# schemaElec_Protomesure.net
KiCad netlist of a schematic drawn in EAGLE
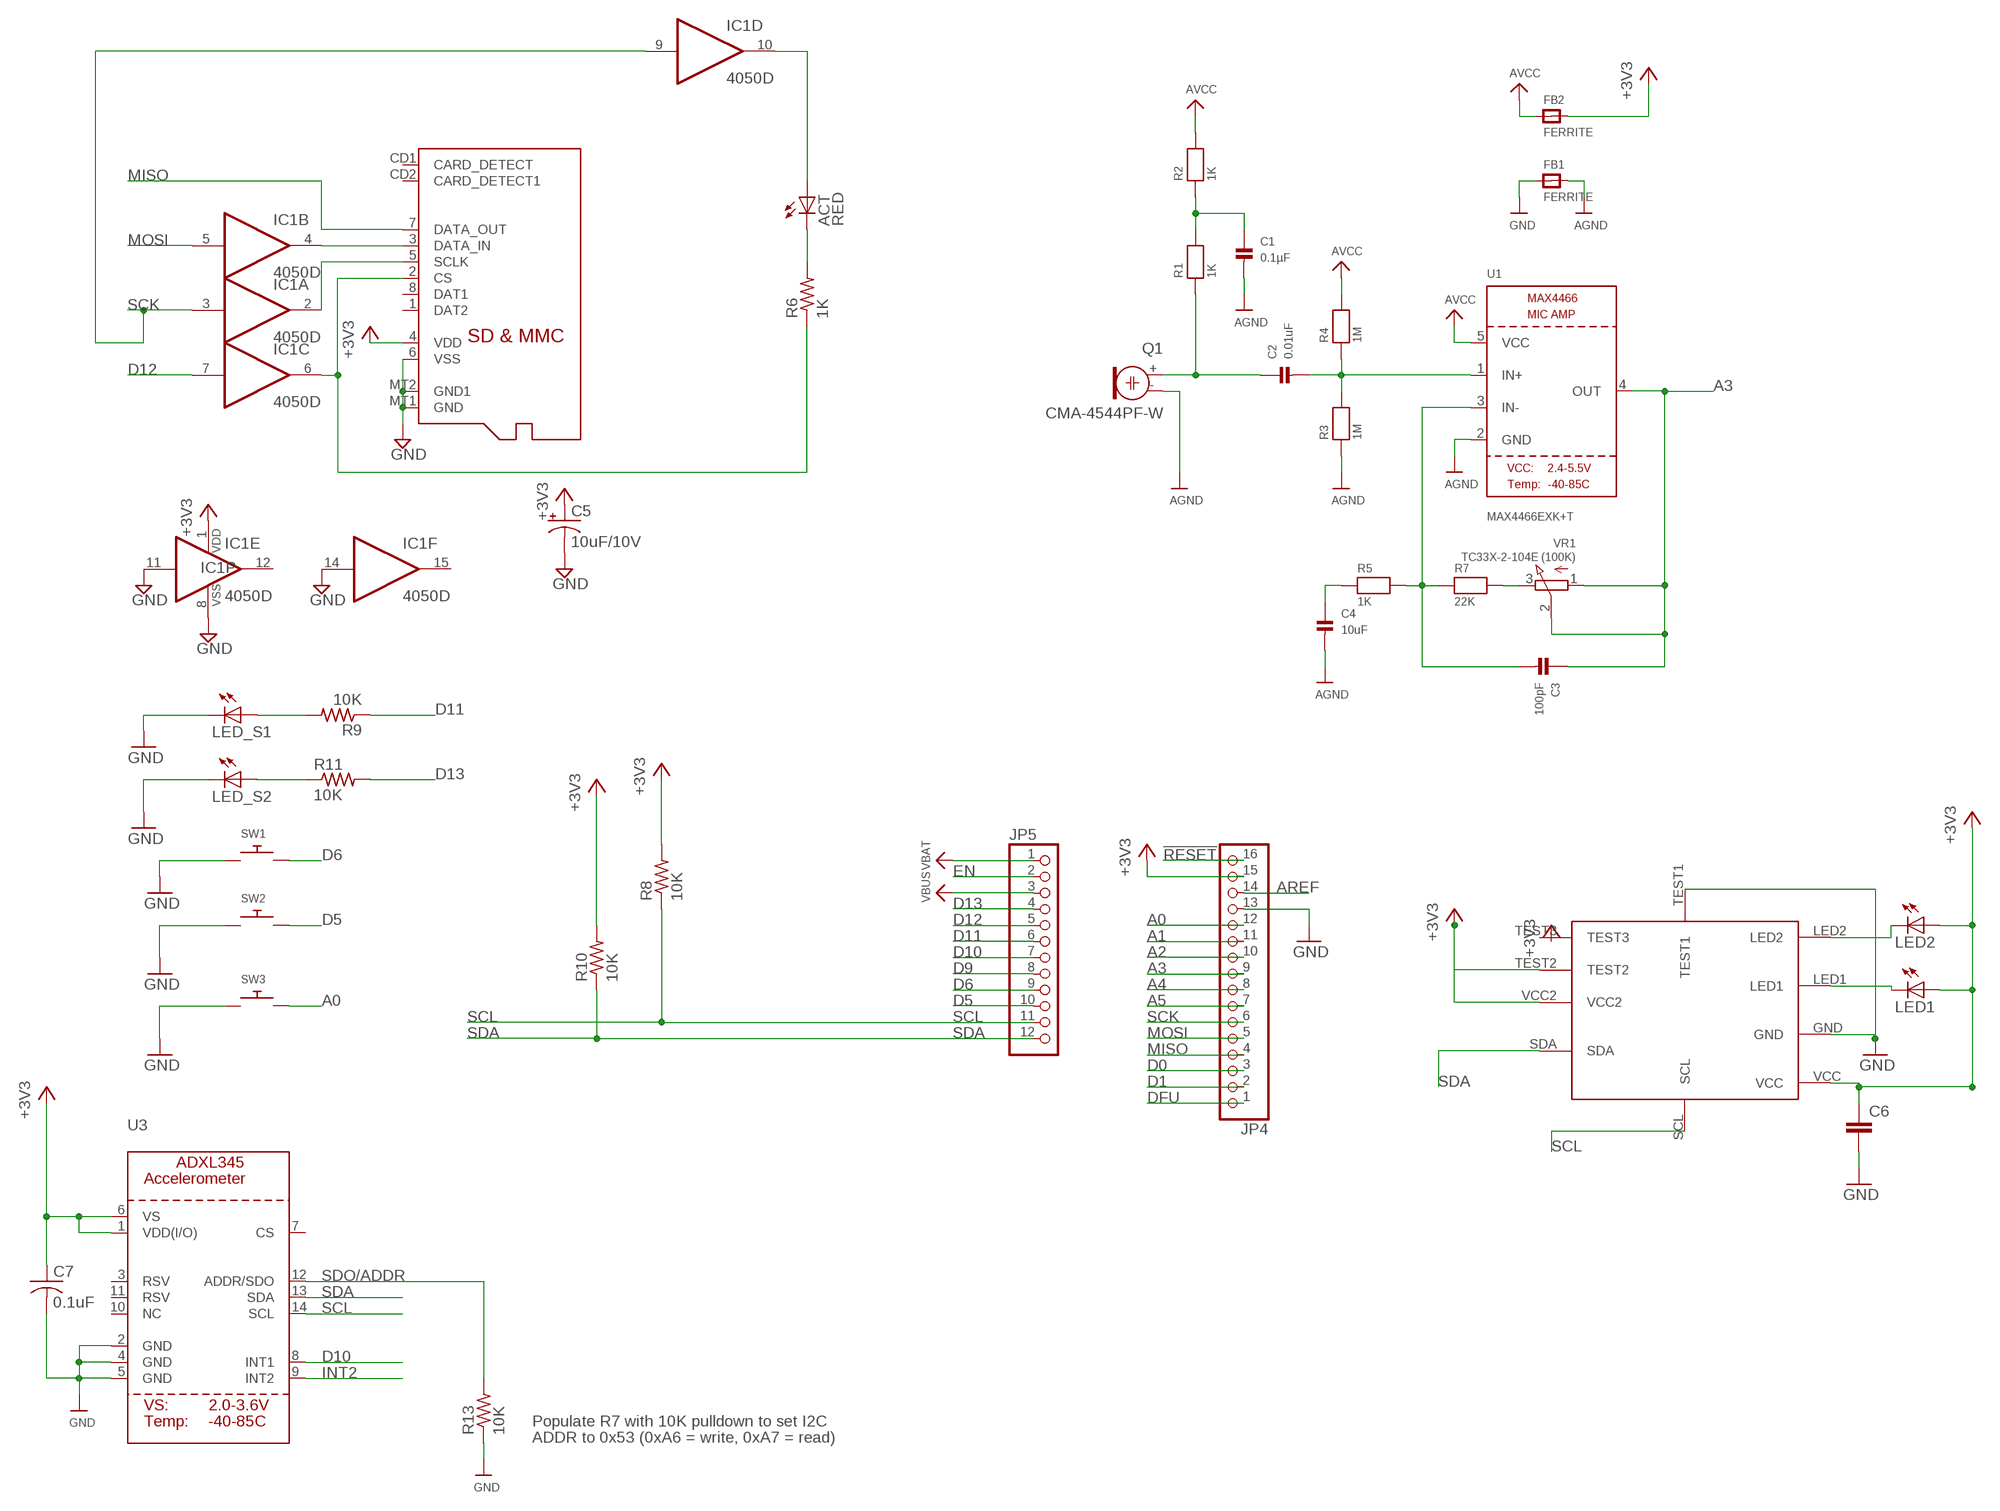
[diagram p0: schematic, sheet 1]

(export (version "E")
  (design (tool "Eeschema 10.0.6"))
  (components
    (comp (ref "ACT")
      (value "RED")
      (footprint "eagle-import:CHIP-LED0805")
      (libsource (lib "eagle-import") (part "LEDCHIP-LED0805"))
    )
    (comp (ref "C1")
      (value "0.1µF")
      (footprint "eagle-import:0805")
      (libsource (lib "eagle-import") (part "CAP_CERAMIC0805"))
    )
    (comp (ref "C2")
      (value "0.01uF")
      (footprint "eagle-import:0805")
      (libsource (lib "eagle-import") (part "CAP_CERAMIC0805"))
    )
    (comp (ref "C3")
      (value "100pF")
      (footprint "eagle-import:0805")
      (libsource (lib "eagle-import") (part "CAP_CERAMIC0805"))
    )
    (comp (ref "C4")
      (value "10uF")
      (footprint "eagle-import:0805")
      (libsource (lib "eagle-import") (part "CAP_CERAMIC0805"))
    )
    (comp (ref "C5")
      (value "10uF/10V")
      (footprint "eagle-import:A_3216-18R")
      (libsource (lib "eagle-import") (part "CPOL-USA/3216-18R"))
    )
    (comp (ref "C6")
      (value "C-EUC0805")
      (footprint "eagle-import:C0805")
      (libsource (lib "eagle-import") (part "C-EUC0805"))
    )
    (comp (ref "C7")
      (value "0.1uF")
      (footprint "eagle-import:C0805")
      (libsource (lib "eagle-import") (part "C-USC0805"))
    )
    (comp (ref "FB1")
      (value "FERRITE")
      (footprint "eagle-import:0805")
      (libsource (lib "eagle-import") (part "FERRITE0805"))
    )
    (comp (ref "FB2")
      (value "FERRITE")
      (footprint "eagle-import:0805")
      (libsource (lib "eagle-import") (part "FERRITE0805"))
    )
    (comp (ref "IC1")
      (value "4050D")
      (footprint "eagle-import:SO16")
      (libsource (lib "eagle-import") (part "4050D"))
    )
    (comp (ref "JP4")
      (value "HEADER-1X16ROUND")
      (footprint "eagle-import:1X16_ROUND")
      (libsource (lib "eagle-import") (part "HEADER-1X16ROUND"))
    )
    (comp (ref "JP5")
      (value "HEADER-1X12")
      (footprint "eagle-import:1X12_ROUND")
      (libsource (lib "eagle-import") (part "HEADER-1X12"))
    )
    (comp (ref "LED1")
      (value "LEDCHIPLED_0805")
      (footprint "eagle-import:CHIPLED_0805")
      (libsource (lib "eagle-import") (part "LEDCHIPLED_0805"))
    )
    (comp (ref "LED2")
      (value "LEDCHIPLED_0805")
      (footprint "eagle-import:CHIPLED_0805")
      (libsource (lib "eagle-import") (part "LEDCHIPLED_0805"))
    )
    (comp (ref "LED_S1")
      (value "LEDCHIPLED_0805")
      (footprint "eagle-import:CHIPLED_0805")
      (libsource (lib "eagle-import") (part "LEDCHIPLED_0805"))
    )
    (comp (ref "LED_S2")
      (value "LEDCHIPLED_0805")
      (footprint "eagle-import:CHIPLED_0805")
      (libsource (lib "eagle-import") (part "LEDCHIPLED_0805"))
    )
    (comp (ref "Q1")
      (value "CMA-4544PF-W")
      (footprint "eagle-import:ELECTRET_9.7")
      (libsource (lib "eagle-import") (part "ELECTRET"))
    )
    (comp (ref "R1")
      (value "1K")
      (footprint "eagle-import:0805")
      (libsource (lib "eagle-import") (part "RESISTOR0805"))
    )
    (comp (ref "R2")
      (value "1K")
      (footprint "eagle-import:0805")
      (libsource (lib "eagle-import") (part "RESISTOR0805"))
    )
    (comp (ref "R3")
      (value "1M")
      (footprint "eagle-import:0805")
      (libsource (lib "eagle-import") (part "RESISTOR0805"))
    )
    (comp (ref "R4")
      (value "1M")
      (footprint "eagle-import:0805")
      (libsource (lib "eagle-import") (part "RESISTOR0805"))
    )
    (comp (ref "R5")
      (value "1K")
      (footprint "eagle-import:0805")
      (libsource (lib "eagle-import") (part "RESISTOR0805"))
    )
    (comp (ref "R6")
      (value "1K")
      (footprint "eagle-import:R0805")
      (libsource (lib "eagle-import") (part "R-US_R0805"))
    )
    (comp (ref "R7")
      (value "22K")
      (footprint "eagle-import:0805")
      (libsource (lib "eagle-import") (part "RESISTOR0805"))
    )
    (comp (ref "R8")
      (value "10K")
      (footprint "eagle-import:R0805")
      (libsource (lib "eagle-import") (part "R-US_R0805"))
    )
    (comp (ref "R9")
      (value "10K")
      (footprint "eagle-import:R0805")
      (libsource (lib "eagle-import") (part "R-US_R0805"))
    )
    (comp (ref "R10")
      (value "10K")
      (footprint "eagle-import:R0805")
      (libsource (lib "eagle-import") (part "R-US_R0805"))
    )
    (comp (ref "R11")
      (value "10K")
      (footprint "eagle-import:R0805")
      (libsource (lib "eagle-import") (part "R-US_R0805"))
    )
    (comp (ref "R13")
      (value "10K")
      (footprint "eagle-import:R0805")
      (libsource (lib "eagle-import") (part "R-US_R0805"))
    )
    (comp (ref "SW1")
      (value "SWITCH_PUSHBUTTONEVQ-PE")
      (footprint "eagle-import:TACT_PANA-EVQ")
      (libsource (lib "eagle-import") (part "SWITCH_PUSHBUTTONEVQ-PE"))
    )
    (comp (ref "SW2")
      (value "SWITCH_PUSHBUTTONEVQ-PE")
      (footprint "eagle-import:TACT_PANA-EVQ")
      (libsource (lib "eagle-import") (part "SWITCH_PUSHBUTTONEVQ-PE"))
    )
    (comp (ref "SW3")
      (value "SWITCH_PUSHBUTTONEVQ-PE")
      (footprint "eagle-import:TACT_PANA-EVQ")
      (libsource (lib "eagle-import") (part "SWITCH_PUSHBUTTONEVQ-PE"))
    )
    (comp (ref "U$31")
      (value "BH1790")
      (footprint "eagle-import:BH1790")
      (libsource (lib "eagle-import") (part "BH1790"))
    )
    (comp (ref "U1")
      (value "MAX4466EXK+T")
      (footprint "eagle-import:SC70-5")
      (libsource (lib "eagle-import") (part "MAX4466{dblquote}{dblquote}"))
    )
    (comp (ref "U3")
      (value "ACCEL_ADXL345")
      (footprint "eagle-import:LGA14")
      (libsource (lib "eagle-import") (part "ACCEL_ADXL345"))
    )
    (comp (ref "VR1")
      (value "TC33X-2-104E (100K)")
      (footprint "eagle-import:TRIMPOT_BOURNS_TC33X-2")
      (libsource (lib "eagle-import") (part "TRIMPOTTC33X-2"))
    )
    (comp (ref "X1")
      (value "MICROSD")
      (footprint "eagle-import:MICROSD")
      (libsource (lib "eagle-import") (part "MICROSD"))
    )
  )
  (nets
    (net (code "1") (name "+3V3") (class "Default")
      (node (ref "C5") (pin "+") (pinfunction "+_+") (pintype "passive"))
      (node (ref "C6") (pin "1") (pinfunction "1_1") (pintype "passive"))
      (node (ref "C7") (pin "1") (pinfunction "1_1") (pintype "passive"))
      (node (ref "FB2") (pin "2") (pinfunction "P$2_2") (pintype "passive"))
      (node (ref "IC1") (pin "1") (pinfunction "VDD_1") (pintype "power_in"))
      (node (ref "JP4") (pin "15") (pinfunction "15_15") (pintype "passive"))
      (node (ref "LED1") (pin "A") (pinfunction "A_A") (pintype "passive"))
      (node (ref "LED2") (pin "A") (pinfunction "A_A") (pintype "passive"))
      (node (ref "R10") (pin "2") (pinfunction "2_2") (pintype "passive"))
      (node (ref "R8") (pin "2") (pinfunction "2_2") (pintype "passive"))
      (node (ref "U$31") (pin "TEST2") (pinfunction "TEST2_TEST2") (pintype "bidirectional"))
      (node (ref "U$31") (pin "VCC") (pinfunction "VCC_VCC") (pintype "bidirectional"))
      (node (ref "U$31") (pin "VCC2") (pinfunction "VCC2_VCC2") (pintype "bidirectional"))
      (node (ref "U3") (pin "1") (pinfunction "VDD(I/O)_1") (pintype "bidirectional"))
      (node (ref "U3") (pin "6") (pinfunction "VS_6") (pintype "bidirectional"))
      (node (ref "X1") (pin "4") (pinfunction "VDD_4") (pintype "power_in"))
    )
    (net (code "2") (name "/A0") (class "Default")
      (node (ref "JP4") (pin "12") (pinfunction "12_12") (pintype "passive"))
      (node (ref "SW3") (pin "P$2") (pinfunction "P$2_P$2") (pintype "passive"))
    )
    (net (code "3") (name "/A1") (class "Default")
      (node (ref "JP4") (pin "11") (pinfunction "11_11") (pintype "passive"))
    )
    (net (code "4") (name "/A2") (class "Default")
      (node (ref "JP4") (pin "10") (pinfunction "10_10") (pintype "passive"))
    )
    (net (code "5") (name "/A3") (class "Default")
      (node (ref "C3") (pin "1") (pinfunction "P$1_1") (pintype "passive"))
      (node (ref "JP4") (pin "9") (pinfunction "9_9") (pintype "passive"))
      (node (ref "U1") (pin "4") (pinfunction "OUT_4") (pintype "bidirectional"))
      (node (ref "VR1") (pin "1") (pinfunction "A_1") (pintype "passive"))
      (node (ref "VR1") (pin "2") (pinfunction "S_2") (pintype "passive"))
    )
    (net (code "6") (name "/A4") (class "Default")
      (node (ref "JP4") (pin "8") (pinfunction "8_8") (pintype "passive"))
    )
    (net (code "7") (name "/A5") (class "Default")
      (node (ref "JP4") (pin "7") (pinfunction "7_7") (pintype "passive"))
    )
    (net (code "8") (name "/AREF") (class "Default")
      (node (ref "JP4") (pin "14") (pinfunction "14_14") (pintype "passive"))
    )
    (net (code "9") (name "/D0") (class "Default")
      (node (ref "JP4") (pin "3") (pinfunction "3_3") (pintype "passive"))
    )
    (net (code "10") (name "/D1") (class "Default")
      (node (ref "JP4") (pin "2") (pinfunction "2_2") (pintype "passive"))
    )
    (net (code "11") (name "/D5") (class "Default")
      (node (ref "JP5") (pin "10") (pinfunction "10_10") (pintype "passive"))
      (node (ref "SW2") (pin "P$2") (pinfunction "P$2_P$2") (pintype "passive"))
    )
    (net (code "12") (name "/D6") (class "Default")
      (node (ref "JP5") (pin "9") (pinfunction "9_9") (pintype "passive"))
      (node (ref "SW1") (pin "P$2") (pinfunction "P$2_P$2") (pintype "passive"))
    )
    (net (code "13") (name "/D9") (class "Default")
      (node (ref "JP5") (pin "8") (pinfunction "8_8") (pintype "passive"))
    )
    (net (code "14") (name "/D10") (class "Default")
      (node (ref "JP5") (pin "7") (pinfunction "7_7") (pintype "passive"))
      (node (ref "U3") (pin "8") (pinfunction "INT1_8") (pintype "bidirectional"))
    )
    (net (code "15") (name "/D11") (class "Default")
      (node (ref "JP5") (pin "6") (pinfunction "6_6") (pintype "passive"))
      (node (ref "R9") (pin "1") (pinfunction "1_1") (pintype "passive"))
    )
    (net (code "16") (name "/D12") (class "Default")
      (node (ref "IC1") (pin "7") (pinfunction "I_7") (pintype "input"))
      (node (ref "JP5") (pin "5") (pinfunction "5_5") (pintype "passive"))
    )
    (net (code "17") (name "/D13") (class "Default")
      (node (ref "JP5") (pin "4") (pinfunction "4_4") (pintype "passive"))
      (node (ref "R11") (pin "2") (pinfunction "2_2") (pintype "passive"))
    )
    (net (code "18") (name "/DFU") (class "Default")
      (node (ref "JP4") (pin "1") (pinfunction "1_1") (pintype "passive"))
    )
    (net (code "19") (name "/EN") (class "Default")
      (node (ref "JP5") (pin "2") (pinfunction "2_2") (pintype "passive"))
    )
    (net (code "20") (name "/INT2") (class "Default")
      (node (ref "U3") (pin "9") (pinfunction "INT2_9") (pintype "bidirectional"))
    )
    (net (code "21") (name "/MISO") (class "Default")
      (node (ref "JP4") (pin "4") (pinfunction "4_4") (pintype "passive"))
      (node (ref "X1") (pin "7") (pinfunction "DATA_OUT_7") (pintype "output"))
    )
    (net (code "22") (name "/MOSI") (class "Default")
      (node (ref "IC1") (pin "5") (pinfunction "I_5") (pintype "input"))
      (node (ref "JP4") (pin "5") (pinfunction "5_5") (pintype "passive"))
    )
    (net (code "23") (name "/SCK") (class "Default")
      (node (ref "IC1") (pin "3") (pinfunction "I_3") (pintype "input"))
      (node (ref "IC1") (pin "9") (pinfunction "I_9") (pintype "input"))
      (node (ref "JP4") (pin "6") (pinfunction "6_6") (pintype "passive"))
    )
    (net (code "24") (name "/SCL") (class "Default")
      (node (ref "JP5") (pin "11") (pinfunction "11_11") (pintype "passive"))
      (node (ref "R8") (pin "1") (pinfunction "1_1") (pintype "passive"))
      (node (ref "U$31") (pin "SCL") (pinfunction "SCL_SCL") (pintype "bidirectional"))
      (node (ref "U3") (pin "14") (pinfunction "SCL_14") (pintype "bidirectional"))
    )
    (net (code "25") (name "/SDA") (class "Default")
      (node (ref "JP5") (pin "12") (pinfunction "12_12") (pintype "passive"))
      (node (ref "R10") (pin "1") (pinfunction "1_1") (pintype "passive"))
      (node (ref "U$31") (pin "SDA") (pinfunction "SDA_SDA") (pintype "bidirectional"))
      (node (ref "U3") (pin "13") (pinfunction "SDA_13") (pintype "bidirectional"))
    )
    (net (code "26") (name "/SDO{slash}ADDR") (class "Default")
      (node (ref "R13") (pin "2") (pinfunction "2_2") (pintype "passive"))
      (node (ref "U3") (pin "12") (pinfunction "ADDR/SDO_12") (pintype "bidirectional"))
    )
    (net (code "27") (name "/~{RESET}") (class "Default")
      (node (ref "JP4") (pin "16") (pinfunction "16_16") (pintype "passive"))
    )
    (net (code "28") (name "AGND") (class "Default")
      (node (ref "C1") (pin "2") (pinfunction "P$2_2") (pintype "passive"))
      (node (ref "C4") (pin "2") (pinfunction "P$2_2") (pintype "passive"))
      (node (ref "FB1") (pin "2") (pinfunction "P$2_2") (pintype "passive"))
      (node (ref "Q1") (pin "-") (pinfunction "1_-") (pintype "passive"))
      (node (ref "R3") (pin "1") (pinfunction "1_1") (pintype "passive"))
      (node (ref "U1") (pin "2") (pinfunction "GND_2") (pintype "bidirectional"))
    )
    (net (code "29") (name "AVCC") (class "Default")
      (node (ref "FB2") (pin "1") (pinfunction "P$1_1") (pintype "passive"))
      (node (ref "R2") (pin "2") (pinfunction "2_2") (pintype "passive"))
      (node (ref "R4") (pin "2") (pinfunction "2_2") (pintype "passive"))
      (node (ref "U1") (pin "5") (pinfunction "VCC_5") (pintype "bidirectional"))
    )
    (net (code "30") (name "GND") (class "Default")
      (node (ref "C5") (pin "-") (pinfunction "-_-") (pintype "passive"))
      (node (ref "C6") (pin "2") (pinfunction "2_2") (pintype "passive"))
      (node (ref "C7") (pin "2") (pinfunction "2_2") (pintype "passive"))
      (node (ref "FB1") (pin "1") (pinfunction "P$1_1") (pintype "passive"))
      (node (ref "IC1") (pin "11") (pinfunction "I_11") (pintype "input"))
      (node (ref "IC1") (pin "14") (pinfunction "I_14") (pintype "input"))
      (node (ref "IC1") (pin "8") (pinfunction "VSS_8") (pintype "power_in"))
      (node (ref "JP4") (pin "13") (pinfunction "13_13") (pintype "passive"))
      (node (ref "LED_S1") (pin "C") (pinfunction "C_C") (pintype "passive"))
      (node (ref "LED_S2") (pin "C") (pinfunction "C_C") (pintype "passive"))
      (node (ref "R13") (pin "1") (pinfunction "1_1") (pintype "passive"))
      (node (ref "SW1") (pin "P$1") (pinfunction "P$1_P$1") (pintype "passive"))
      (node (ref "SW2") (pin "P$1") (pinfunction "P$1_P$1") (pintype "passive"))
      (node (ref "SW3") (pin "P$1") (pinfunction "P$1_P$1") (pintype "passive"))
      (node (ref "U$31") (pin "GND") (pinfunction "GND_GND") (pintype "bidirectional"))
      (node (ref "U$31") (pin "TEST1") (pinfunction "TEST1_TEST1") (pintype "bidirectional"))
      (node (ref "U3") (pin "2") (pinfunction "GND_2") (pintype "bidirectional"))
      (node (ref "U3") (pin "4") (pinfunction "GND_4") (pintype "bidirectional"))
      (node (ref "U3") (pin "5") (pinfunction "GND_5") (pintype "bidirectional"))
      (node (ref "X1") (pin "6") (pinfunction "VSS_6") (pintype "power_in"))
      (node (ref "X1") (pin "MT1") (pinfunction "GND_MT1") (pintype "power_in"))
      (node (ref "X1") (pin "MT2") (pinfunction "GND1_MT2") (pintype "power_in"))
    )
    (net (code "31") (name "Net-(ACT-PadC)") (class "Default")
      (node (ref "ACT") (pin "C") (pinfunction "C_C") (pintype "passive"))
      (node (ref "R6") (pin "2") (pinfunction "2_2") (pintype "passive"))
    )
    (net (code "32") (name "Net-(C1-P$1)") (class "Default")
      (node (ref "C1") (pin "1") (pinfunction "P$1_1") (pintype "passive"))
      (node (ref "R1") (pin "2") (pinfunction "2_2") (pintype "passive"))
      (node (ref "R2") (pin "1") (pinfunction "1_1") (pintype "passive"))
    )
    (net (code "33") (name "Net-(C2-P$1)") (class "Default")
      (node (ref "C2") (pin "1") (pinfunction "P$1_1") (pintype "passive"))
      (node (ref "Q1") (pin "+") (pinfunction "2_+") (pintype "passive"))
      (node (ref "R1") (pin "1") (pinfunction "1_1") (pintype "passive"))
    )
    (net (code "34") (name "Net-(C2-P$2)") (class "Default")
      (node (ref "C2") (pin "2") (pinfunction "P$2_2") (pintype "passive"))
      (node (ref "R3") (pin "2") (pinfunction "2_2") (pintype "passive"))
      (node (ref "R4") (pin "1") (pinfunction "1_1") (pintype "passive"))
      (node (ref "U1") (pin "1") (pinfunction "IN+_1") (pintype "bidirectional"))
    )
    (net (code "35") (name "Net-(C3-P$2)") (class "Default")
      (node (ref "C3") (pin "2") (pinfunction "P$2_2") (pintype "passive"))
      (node (ref "R5") (pin "2") (pinfunction "2_2") (pintype "passive"))
      (node (ref "R7") (pin "1") (pinfunction "1_1") (pintype "passive"))
      (node (ref "U1") (pin "3") (pinfunction "IN-_3") (pintype "bidirectional"))
    )
    (net (code "36") (name "Net-(C4-P$1)") (class "Default")
      (node (ref "C4") (pin "1") (pinfunction "P$1_1") (pintype "passive"))
      (node (ref "R5") (pin "1") (pinfunction "1_1") (pintype "passive"))
    )
    (net (code "37") (name "Net-(IC1A-O)") (class "Default")
      (node (ref "IC1") (pin "2") (pinfunction "O_2") (pintype "output"))
      (node (ref "X1") (pin "5") (pinfunction "SCLK_5") (pintype "input"))
    )
    (net (code "38") (name "Net-(IC1B-O)") (class "Default")
      (node (ref "IC1") (pin "4") (pinfunction "O_4") (pintype "output"))
      (node (ref "X1") (pin "3") (pinfunction "DATA_IN_3") (pintype "input"))
    )
    (net (code "39") (name "Net-(IC1C-O)") (class "Default")
      (node (ref "IC1") (pin "6") (pinfunction "O_6") (pintype "output"))
      (node (ref "R6") (pin "1") (pinfunction "1_1") (pintype "passive"))
      (node (ref "X1") (pin "2") (pinfunction "CS_2") (pintype "input"))
    )
    (net (code "40") (name "Net-(IC1D-O)") (class "Default")
      (node (ref "ACT") (pin "A") (pinfunction "A_A") (pintype "passive"))
      (node (ref "IC1") (pin "10") (pinfunction "O_10") (pintype "output"))
    )
    (net (code "41") (name "Net-(LED1-PadC)") (class "Default")
      (node (ref "LED1") (pin "C") (pinfunction "C_C") (pintype "passive"))
      (node (ref "U$31") (pin "LED1") (pinfunction "LED1_LED1") (pintype "bidirectional"))
    )
    (net (code "42") (name "Net-(LED2-PadC)") (class "Default")
      (node (ref "LED2") (pin "C") (pinfunction "C_C") (pintype "passive"))
      (node (ref "U$31") (pin "LED2") (pinfunction "LED2_LED2") (pintype "bidirectional"))
    )
    (net (code "43") (name "Net-(LED_S1-PadA)") (class "Default")
      (node (ref "LED_S1") (pin "A") (pinfunction "A_A") (pintype "passive"))
      (node (ref "R9") (pin "2") (pinfunction "2_2") (pintype "passive"))
    )
    (net (code "44") (name "Net-(LED_S2-PadA)") (class "Default")
      (node (ref "LED_S2") (pin "A") (pinfunction "A_A") (pintype "passive"))
      (node (ref "R11") (pin "1") (pinfunction "1_1") (pintype "passive"))
    )
    (net (code "45") (name "Net-(VR1-E)") (class "Default")
      (node (ref "R7") (pin "2") (pinfunction "2_2") (pintype "passive"))
      (node (ref "VR1") (pin "3") (pinfunction "E_3") (pintype "passive"))
    )
    (net (code "46") (name "VBAT") (class "Default")
      (node (ref "JP5") (pin "1") (pinfunction "1_1") (pintype "passive"))
    )
    (net (code "47") (name "VBUS") (class "Default")
      (node (ref "JP5") (pin "3") (pinfunction "3_3") (pintype "passive"))
    )
    (net (code "48") (name "unconnected-(IC1E-O-Pad12)") (class "Default")
      (node (ref "IC1") (pin "12") (pinfunction "O_12") (pintype "output"))
    )
    (net (code "49") (name "unconnected-(IC1F-O-Pad15)") (class "Default")
      (node (ref "IC1") (pin "15") (pinfunction "O_15") (pintype "output"))
    )
    (net (code "50") (name "unconnected-(U$31-PadTEST3)") (class "Default")
      (node (ref "U$31") (pin "TEST3") (pinfunction "TEST3_TEST3") (pintype "bidirectional"))
    )
    (net (code "51") (name "unconnected-(U3-CS-Pad7)") (class "Default")
      (node (ref "U3") (pin "7") (pinfunction "CS_7") (pintype "bidirectional"))
    )
    (net (code "52") (name "unconnected-(U3-NC-Pad10)") (class "Default")
      (node (ref "U3") (pin "10") (pinfunction "NC_10") (pintype "bidirectional"))
    )
    (net (code "53") (name "unconnected-(U3-RSV-Pad3)") (class "Default")
      (node (ref "U3") (pin "3") (pinfunction "RSV_3") (pintype "bidirectional"))
    )
    (net (code "54") (name "unconnected-(U3-RSV-Pad11)") (class "Default")
      (node (ref "U3") (pin "11") (pinfunction "RSV_11") (pintype "bidirectional"))
    )
    (net (code "55") (name "unconnected-(X1-CARD_DETECT-PadCD1)") (class "Default")
      (node (ref "X1") (pin "CD1") (pinfunction "CARD_DETECT_CD1") (pintype "passive"))
    )
    (net (code "56") (name "unconnected-(X1-CARD_DETECT1-PadCD2)") (class "Default")
      (node (ref "X1") (pin "CD2") (pinfunction "CARD_DETECT1_CD2") (pintype "passive"))
    )
    (net (code "57") (name "unconnected-(X1-DAT1-Pad8)") (class "Default")
      (node (ref "X1") (pin "8") (pinfunction "DAT1_8") (pintype "bidirectional"))
    )
    (net (code "58") (name "unconnected-(X1-DAT2-Pad1)") (class "Default")
      (node (ref "X1") (pin "1") (pinfunction "DAT2_1") (pintype "bidirectional"))
    )
  )
)
